# BQ24392_USB_Switch_w_BC_Det.net
KiCad netlist of a schematic drawn in Altium Designer
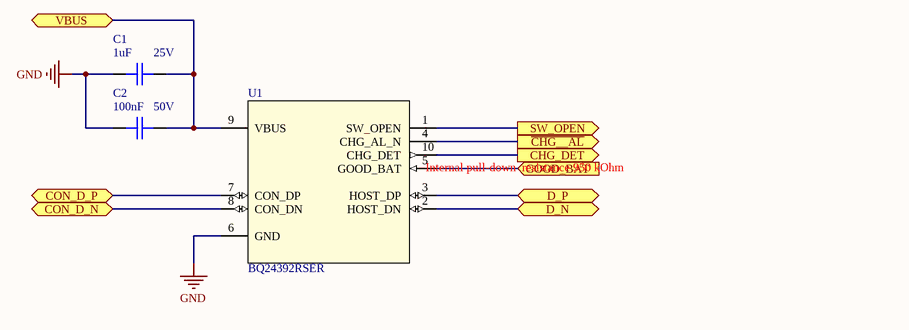
[diagram p0: BQ24392_USB_Switch_w_BC_Det.SchDoc]

(export (version "E")
  (design (tool "Eeschema 10.0.6"))
  (components
    (comp (ref "C1")
      (value "CAP CER 1UF 25V X5R 0603")
      (footprint "C0603")
      (description "1µF ±20% 25V Ceramic Capacitor X5R 0603 (1608 Metric)")
      (fields
        (field (name "MANUFACTURER") "Yageo")
        (field (name "MANUFACTURER PART NUMBER") "CC0603MRX5R8BB105")
        (field (name "CAPACITANCE") "1uF")
        (field (name "VOLTAGE RATING") "25V")
      )
      (libsource (lib "capacitors_smd") (part "CAP CER 1UF 25V X5R 0603"))
    )
    (comp (ref "C2")
      (value "CAP CER 0.1UF 50V X7R 0402")
      (footprint "C0402")
      (description "0.1µF ±10% 50V Ceramic Capacitor X7R 0402 (1005 Metric)")
      (fields
        (field (name "MANUFACTURER") "TDK")
        (field (name "MANUFACTURER PART NUMBER") "CGA2B3X7R1H104K050BB")
        (field (name "CAPACITANCE") "100nF")
        (field (name "VOLTAGE") "50V")
      )
      (libsource (lib "capacitors_smd") (part "CAP CER 0.1UF 50V X7R 0402"))
    )
    (comp (ref "U1")
      (value "BQ24392RSER")
      (footprint "RSE10_TEX")
      (description "Battery Multi-Function Controller IC  10-UQFN (2.0x1.5)")
      (fields (field (name "MANUFACTURER") "Texas Instruments"))
      (libsource (lib "BLDC_Motor_Driver") (part "IC BQ24392RSER CHARGE DETECT HS USB 10UQFN"))
    )
  )
  (nets
    (net (code "1") (name "/CHG_DET") (class "Default")
      (node (ref "U1") (pin "10") (pinfunction "CHG_DET_10") (pintype "output"))
    )
    (net (code "2") (name "/CHG__AL") (class "Default")
      (node (ref "U1") (pin "4") (pinfunction "CHG_AL_N_4") (pintype "open_collector"))
    )
    (net (code "3") (name "/CON_D_N") (class "Default")
      (node (ref "U1") (pin "8") (pinfunction "CON_DN_8") (pintype "bidirectional"))
    )
    (net (code "4") (name "/CON_D_P") (class "Default")
      (node (ref "U1") (pin "7") (pinfunction "CON_DP_7") (pintype "bidirectional"))
    )
    (net (code "5") (name "/D_N") (class "Default")
      (node (ref "U1") (pin "2") (pinfunction "HOST_DN_2") (pintype "bidirectional"))
    )
    (net (code "6") (name "/D_P") (class "Default")
      (node (ref "U1") (pin "3") (pinfunction "HOST_DP_3") (pintype "bidirectional"))
    )
    (net (code "7") (name "/GOOD_BAT") (class "Default")
      (node (ref "U1") (pin "5") (pinfunction "GOOD_BAT_5") (pintype "input"))
    )
    (net (code "8") (name "/SW_OPEN") (class "Default")
      (node (ref "U1") (pin "1") (pinfunction "SW_OPEN_1") (pintype "open_collector"))
    )
    (net (code "9") (name "/VBUS") (class "Default")
      (node (ref "C1") (pin "1") (pinfunction "1_1") (pintype "passive"))
      (node (ref "C2") (pin "1") (pinfunction "1_1") (pintype "passive"))
      (node (ref "U1") (pin "9") (pinfunction "VBUS_9") (pintype "power_in"))
    )
    (net (code "10") (name "GND") (class "Default")
      (node (ref "C1") (pin "2") (pinfunction "2_2") (pintype "passive"))
      (node (ref "C2") (pin "2") (pinfunction "2_2") (pintype "passive"))
      (node (ref "U1") (pin "6") (pinfunction "GND_6") (pintype "power_in"))
    )
  )
)
